# minishiled_smd.net
KiCad netlist of a schematic drawn in EAGLE
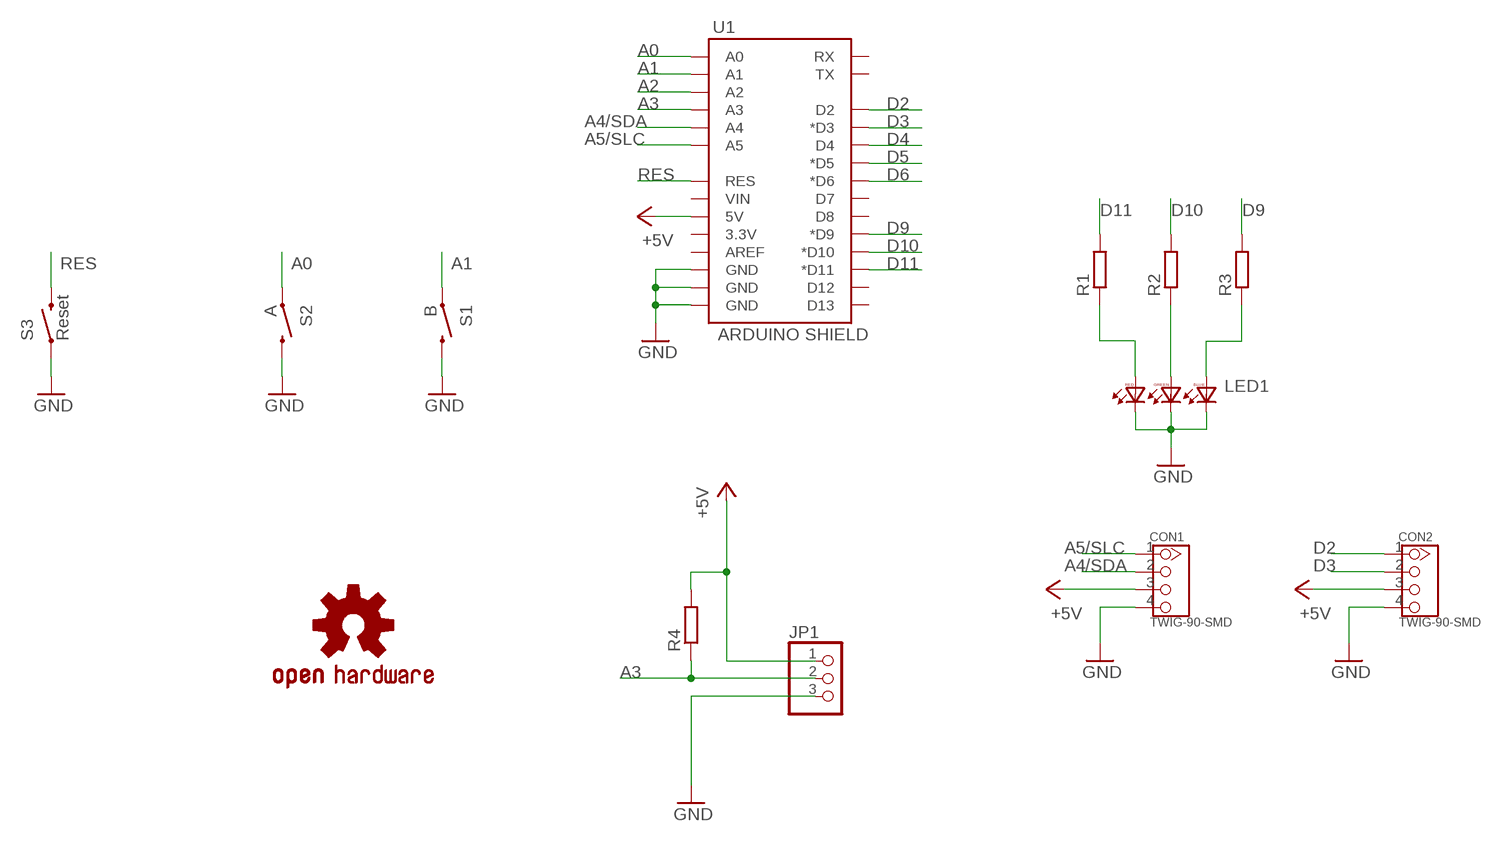
[diagram p0: schematic, sheet 1]

(export (version "E")
  (design (tool "Eeschema 10.0.6"))
  (components
    (comp (ref "CON1")
      (value "TWIG-90-SMD")
      (footprint "eagle-import:TWIG-90-SMD")
      (libsource (lib "eagle-import") (part "TWIG-90-SMD"))
    )
    (comp (ref "CON2")
      (value "TWIG-90-SMD")
      (footprint "eagle-import:TWIG-90-SMD")
      (libsource (lib "eagle-import") (part "TWIG-90-SMD"))
    )
    (comp (ref "JP1")
      (value "PINHD-1X3")
      (footprint "eagle-import:1X03")
      (libsource (lib "eagle-import") (part "PINHD-1X3"))
    )
    (comp (ref "LED1")
      (value "LED-RGB-PLCC6")
      (footprint "eagle-import:PLCC6-RAW")
      (libsource (lib "eagle-import") (part "LED-RGB-PLCC6"))
    )
    (comp (ref "R1")
      (value "R-EU_R1206")
      (footprint "eagle-import:R1206")
      (libsource (lib "eagle-import") (part "R-EU_R1206"))
    )
    (comp (ref "R2")
      (value "R-EU_R1206")
      (footprint "eagle-import:R1206")
      (libsource (lib "eagle-import") (part "R-EU_R1206"))
    )
    (comp (ref "R3")
      (value "R-EU_R1206")
      (footprint "eagle-import:R1206")
      (libsource (lib "eagle-import") (part "R-EU_R1206"))
    )
    (comp (ref "R4")
      (value "R-EU_R1206")
      (footprint "eagle-import:R1206")
      (libsource (lib "eagle-import") (part "R-EU_R1206"))
    )
    (comp (ref "S1")
      (value "B")
      (footprint "eagle-import:TACTILE_SWITCH_TALL")
      (libsource (lib "eagle-import") (part "SWITCH-MOMENTARY-2"))
    )
    (comp (ref "S2")
      (value "A")
      (footprint "eagle-import:TACTILE_SWITCH_TALL")
      (libsource (lib "eagle-import") (part "SWITCH-MOMENTARY-2"))
    )
    (comp (ref "S3")
      (value "Reset")
      (footprint "eagle-import:TACTILE-SWITCH-1101NE")
      (libsource (lib "eagle-import") (part "SWITCH-MOMENTARY-2-SMD-1101NE"))
    )
    (comp (ref "U$1")
      (value "LOGO-OSH")
      (footprint "eagle-import:LOGO-OSH")
      (libsource (lib "eagle-import") (part "LOGO-OSH"))
    )
    (comp (ref "U1")
      (value "ARDUINO SHIELD")
      (footprint "eagle-import:DUEMILANOVE_VIAS")
      (libsource (lib "eagle-import") (part "ARDUINO_SHIELDNO_SILK"))
    )
  )
  (nets
    (net (code "1") (name "+5V") (class "Default")
      (node (ref "CON1") (pin "3") (pinfunction "3_3") (pintype "bidirectional"))
      (node (ref "CON2") (pin "3") (pinfunction "3_3") (pintype "bidirectional"))
      (node (ref "JP1") (pin "1") (pinfunction "1_1") (pintype "passive"))
      (node (ref "R4") (pin "2") (pinfunction "2_2") (pintype "passive"))
      (node (ref "U1") (pin "5V") (pinfunction "5V_5V") (pintype "bidirectional"))
    )
    (net (code "2") (name "/A0") (class "Default")
      (node (ref "S2") (pin "A2") (pinfunction "1_A2") (pintype "passive"))
      (node (ref "U1") (pin "A0") (pinfunction "A0_A0") (pintype "bidirectional"))
    )
    (net (code "3") (name "/A1") (class "Default")
      (node (ref "S1") (pin "A2") (pinfunction "1_A2") (pintype "passive"))
      (node (ref "U1") (pin "A1") (pinfunction "A1_A1") (pintype "bidirectional"))
    )
    (net (code "4") (name "/A2") (class "Default")
      (node (ref "U1") (pin "A2") (pinfunction "A2_A2") (pintype "bidirectional"))
    )
    (net (code "5") (name "/A3") (class "Default")
      (node (ref "JP1") (pin "2") (pinfunction "2_2") (pintype "passive"))
      (node (ref "R4") (pin "1") (pinfunction "1_1") (pintype "passive"))
      (node (ref "U1") (pin "A3") (pinfunction "A3_A3") (pintype "bidirectional"))
    )
    (net (code "6") (name "/A4{slash}SDA") (class "Default")
      (node (ref "CON1") (pin "2") (pinfunction "2_2") (pintype "bidirectional"))
      (node (ref "U1") (pin "A4") (pinfunction "A4_A4") (pintype "bidirectional"))
    )
    (net (code "7") (name "/A5{slash}SLC") (class "Default")
      (node (ref "CON1") (pin "1") (pinfunction "1_1") (pintype "bidirectional"))
      (node (ref "U1") (pin "A5") (pinfunction "A5_A5") (pintype "bidirectional"))
    )
    (net (code "8") (name "/D2") (class "Default")
      (node (ref "CON2") (pin "1") (pinfunction "1_1") (pintype "bidirectional"))
      (node (ref "U1") (pin "D2") (pinfunction "D2_D2") (pintype "bidirectional"))
    )
    (net (code "9") (name "/D3") (class "Default")
      (node (ref "CON2") (pin "2") (pinfunction "2_2") (pintype "bidirectional"))
      (node (ref "U1") (pin "D3") (pinfunction "*D3_D3") (pintype "bidirectional"))
    )
    (net (code "10") (name "/D4") (class "Default")
      (node (ref "U1") (pin "D4") (pinfunction "D4_D4") (pintype "bidirectional"))
    )
    (net (code "11") (name "/D5") (class "Default")
      (node (ref "U1") (pin "D5") (pinfunction "*D5_D5") (pintype "bidirectional"))
    )
    (net (code "12") (name "/D6") (class "Default")
      (node (ref "U1") (pin "D6") (pinfunction "*D6_D6") (pintype "bidirectional"))
    )
    (net (code "13") (name "/D9") (class "Default")
      (node (ref "R3") (pin "2") (pinfunction "2_2") (pintype "passive"))
      (node (ref "U1") (pin "D9") (pinfunction "*D9_D9") (pintype "bidirectional"))
    )
    (net (code "14") (name "/D10") (class "Default")
      (node (ref "R2") (pin "2") (pinfunction "2_2") (pintype "passive"))
      (node (ref "U1") (pin "D10") (pinfunction "*D10_D10") (pintype "bidirectional"))
    )
    (net (code "15") (name "/D11") (class "Default")
      (node (ref "R1") (pin "2") (pinfunction "2_2") (pintype "passive"))
      (node (ref "U1") (pin "D11") (pinfunction "*D11_D11") (pintype "bidirectional"))
    )
    (net (code "16") (name "/RES") (class "Default")
      (node (ref "S3") (pin "P$2") (pinfunction "2_P$2") (pintype "passive"))
      (node (ref "U1") (pin "RES") (pinfunction "RES_RES") (pintype "bidirectional"))
    )
    (net (code "17") (name "GND") (class "Default")
      (node (ref "CON1") (pin "4") (pinfunction "4_4") (pintype "bidirectional"))
      (node (ref "CON2") (pin "4") (pinfunction "4_4") (pintype "bidirectional"))
      (node (ref "JP1") (pin "3") (pinfunction "3_3") (pintype "passive"))
      (node (ref "LED1") (pin "4") (pinfunction "BC_4") (pintype "passive"))
      (node (ref "LED1") (pin "5") (pinfunction "GC_5") (pintype "passive"))
      (node (ref "LED1") (pin "6") (pinfunction "RC_6") (pintype "passive"))
      (node (ref "S1") (pin "B2") (pinfunction "2_B2") (pintype "passive"))
      (node (ref "S2") (pin "B2") (pinfunction "2_B2") (pintype "passive"))
      (node (ref "S3") (pin "P$1") (pinfunction "1_P$1") (pintype "passive"))
      (node (ref "U1") (pin "GND@0") (pinfunction "GND_GND@0") (pintype "bidirectional"))
      (node (ref "U1") (pin "GND@1") (pinfunction "GND_GND@1") (pintype "bidirectional"))
      (node (ref "U1") (pin "GND@2") (pinfunction "GND_GND@2") (pintype "bidirectional"))
    )
    (net (code "18") (name "Net-(LED1-BA)") (class "Default")
      (node (ref "LED1") (pin "1") (pinfunction "BA_1") (pintype "passive"))
      (node (ref "R3") (pin "1") (pinfunction "1_1") (pintype "passive"))
    )
    (net (code "19") (name "Net-(LED1-GA)") (class "Default")
      (node (ref "LED1") (pin "2") (pinfunction "GA_2") (pintype "passive"))
      (node (ref "R2") (pin "1") (pinfunction "1_1") (pintype "passive"))
    )
    (net (code "20") (name "Net-(LED1-RA)") (class "Default")
      (node (ref "LED1") (pin "3") (pinfunction "RA_3") (pintype "passive"))
      (node (ref "R1") (pin "1") (pinfunction "1_1") (pintype "passive"))
    )
    (net (code "21") (name "unconnected-(U1-Pad3.3V)") (class "Default")
      (node (ref "U1") (pin "3.3V") (pinfunction "3.3V_3.3V") (pintype "bidirectional"))
    )
    (net (code "22") (name "unconnected-(U1-PadAREF)") (class "Default")
      (node (ref "U1") (pin "AREF") (pinfunction "AREF_AREF") (pintype "bidirectional"))
    )
    (net (code "23") (name "unconnected-(U1-PadD7)") (class "Default")
      (node (ref "U1") (pin "D7") (pinfunction "D7_D7") (pintype "bidirectional"))
    )
    (net (code "24") (name "unconnected-(U1-PadD8)") (class "Default")
      (node (ref "U1") (pin "D8") (pinfunction "D8_D8") (pintype "bidirectional"))
    )
    (net (code "25") (name "unconnected-(U1-PadD12)") (class "Default")
      (node (ref "U1") (pin "D12") (pinfunction "D12_D12") (pintype "bidirectional"))
    )
    (net (code "26") (name "unconnected-(U1-PadD13)") (class "Default")
      (node (ref "U1") (pin "D13") (pinfunction "D13_D13") (pintype "bidirectional"))
    )
    (net (code "27") (name "unconnected-(U1-PadRX)") (class "Default")
      (node (ref "U1") (pin "RX") (pinfunction "RX_RX") (pintype "bidirectional"))
    )
    (net (code "28") (name "unconnected-(U1-PadTX)") (class "Default")
      (node (ref "U1") (pin "TX") (pinfunction "TX_TX") (pintype "bidirectional"))
    )
    (net (code "29") (name "unconnected-(U1-PadVIN)") (class "Default")
      (node (ref "U1") (pin "VIN") (pinfunction "VIN_VIN") (pintype "bidirectional"))
    )
  )
)
